# OpenProg-18F2550-etch.net
KiCad netlist of a schematic drawn in EAGLE
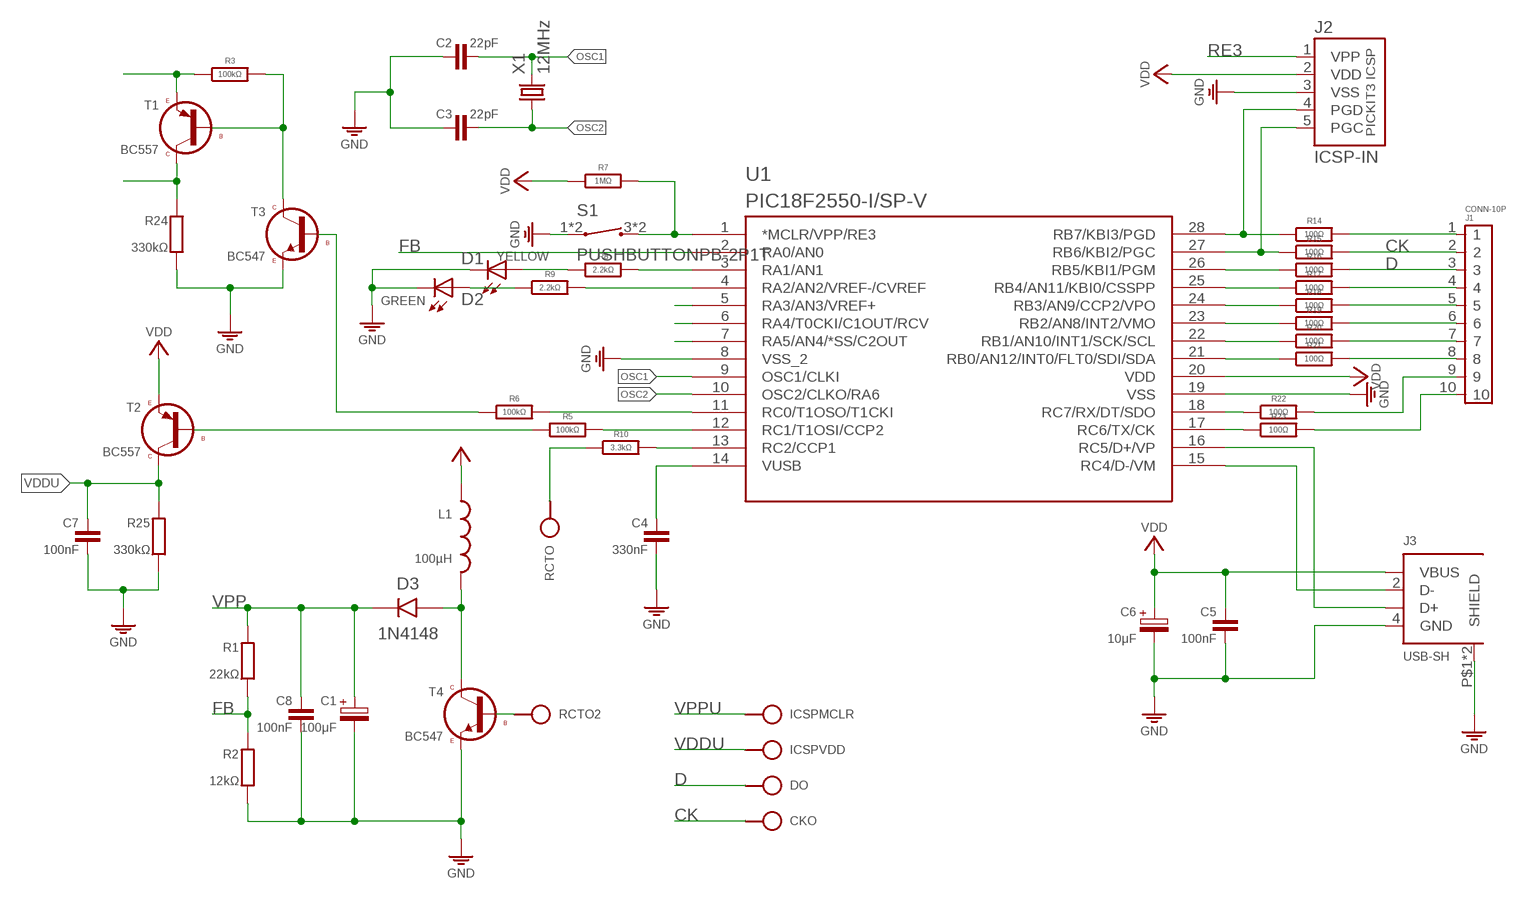
[diagram p0: schematic, sheet 1]

(export (version "E")
  (design (tool "Eeschema 10.0.6"))
  (components
    (comp (ref "C1")
      (value "100μF")
      (footprint "eagle-import:E2,5-5_V")
      (libsource (lib "eagle-import") (part "CPOLE2,5-5/V"))
    )
    (comp (ref "C2")
      (value "22pF")
      (footprint "eagle-import:C025-015X024")
      (libsource (lib "eagle-import") (part "C-H025-015X024"))
    )
    (comp (ref "C3")
      (value "22pF")
      (footprint "eagle-import:C025-015X024")
      (libsource (lib "eagle-import") (part "C-H025-015X024"))
    )
    (comp (ref "C4")
      (value "330nF")
      (footprint "eagle-import:C050-030X075")
      (libsource (lib "eagle-import") (part "C050-030X075"))
    )
    (comp (ref "C5")
      (value "100nF")
      (footprint "eagle-import:C025-015X024")
      (libsource (lib "eagle-import") (part "C025-015X024"))
    )
    (comp (ref "C6")
      (value "10μF")
      (footprint "eagle-import:E2,5-5")
      (libsource (lib "eagle-import") (part "CPOLE2.5-5"))
    )
    (comp (ref "C7")
      (value "100nF")
      (footprint "eagle-import:C025-015X024")
      (libsource (lib "eagle-import") (part "C025-015X024"))
    )
    (comp (ref "C8")
      (value "100nF")
      (footprint "eagle-import:C025-015X024")
      (libsource (lib "eagle-import") (part "C025-015X024"))
    )
    (comp (ref "CKO")
      (value "HPORT")
      (footprint "eagle-import:SPAD")
      (libsource (lib "eagle-import") (part "HPORT"))
    )
    (comp (ref "D1")
      (value "YELLOW")
      (footprint "eagle-import:LED_3MM")
      (libsource (lib "eagle-import") (part "LED-3MM"))
    )
    (comp (ref "D2")
      (value "GREEN")
      (footprint "eagle-import:LED_3MM")
      (libsource (lib "eagle-import") (part "LED-3MM"))
    )
    (comp (ref "D3")
      (value "1N4148")
      (footprint "eagle-import:DO34-7")
      (libsource (lib "eagle-import") (part "1N4148-HDO34-7"))
    )
    (comp (ref "DO")
      (value "HPORT")
      (footprint "eagle-import:SPAD")
      (libsource (lib "eagle-import") (part "HPORT"))
    )
    (comp (ref "ICSPMCLR")
      (value "HPORT")
      (footprint "eagle-import:SPAD")
      (libsource (lib "eagle-import") (part "HPORT"))
    )
    (comp (ref "ICSPVDD")
      (value "HPORT")
      (footprint "eagle-import:SPAD")
      (libsource (lib "eagle-import") (part "HPORT"))
    )
    (comp (ref "J1")
      (value "CONN-10P")
      (footprint "eagle-import:CONN-10P")
      (libsource (lib "eagle-import") (part "CONN-10P"))
    )
    (comp (ref "J2")
      (value "ICSP-IN")
      (footprint "eagle-import:PIC-PK3")
      (libsource (lib "eagle-import") (part "PICKIT3-ICSP-PK3"))
    )
    (comp (ref "J3")
      (value "USB-SH")
      (footprint "eagle-import:USB-B-PRINT")
      (libsource (lib "eagle-import") (part "USB-SH"))
    )
    (comp (ref "L1")
      (value "100µH")
      (footprint "eagle-import:L-03_10V")
      (libsource (lib "eagle-import") (part "L02/10"))
    )
    (comp (ref "R1")
      (value "22kΩ")
      (footprint "eagle-import:0204_10-V")
      (libsource (lib "eagle-import") (part "R0204/10-V"))
    )
    (comp (ref "R2")
      (value "12kΩ")
      (footprint "eagle-import:0204_10-V")
      (libsource (lib "eagle-import") (part "R0204/10-V"))
    )
    (comp (ref "R3")
      (value "100kΩ")
      (footprint "eagle-import:0204_2")
      (libsource (lib "eagle-import") (part "R-H0204/2"))
    )
    (comp (ref "R5")
      (value "100kΩ")
      (footprint "eagle-import:0204_10")
      (libsource (lib "eagle-import") (part "R-H0204/10"))
    )
    (comp (ref "R6")
      (value "100kΩ")
      (footprint "eagle-import:0204_10")
      (libsource (lib "eagle-import") (part "R-H0204/10"))
    )
    (comp (ref "R7")
      (value "1MΩ")
      (footprint "eagle-import:0204_10-V")
      (libsource (lib "eagle-import") (part "R-H0204/10-V"))
    )
    (comp (ref "R8")
      (value "2.2kΩ")
      (footprint "eagle-import:0204_10")
      (libsource (lib "eagle-import") (part "R-H0204/10"))
    )
    (comp (ref "R9")
      (value "2.2kΩ")
      (footprint "eagle-import:0204_10")
      (libsource (lib "eagle-import") (part "R-H0204/10"))
    )
    (comp (ref "R10")
      (value "3.3kΩ")
      (footprint "eagle-import:0204_10")
      (libsource (lib "eagle-import") (part "R-H0204/10"))
    )
    (comp (ref "R14")
      (value "100Ω")
      (footprint "eagle-import:0204_10")
      (libsource (lib "eagle-import") (part "R-H0204/10"))
    )
    (comp (ref "R15")
      (value "100Ω")
      (footprint "eagle-import:0204_10")
      (libsource (lib "eagle-import") (part "R-H0204/10"))
    )
    (comp (ref "R16")
      (value "100Ω")
      (footprint "eagle-import:0204_10")
      (libsource (lib "eagle-import") (part "R-H0204/10"))
    )
    (comp (ref "R17")
      (value "100Ω")
      (footprint "eagle-import:0204_10")
      (libsource (lib "eagle-import") (part "R-H0204/10"))
    )
    (comp (ref "R18")
      (value "100Ω")
      (footprint "eagle-import:0204_10")
      (libsource (lib "eagle-import") (part "R-H0204/10"))
    )
    (comp (ref "R19")
      (value "100Ω")
      (footprint "eagle-import:0204_10")
      (libsource (lib "eagle-import") (part "R-H0204/10"))
    )
    (comp (ref "R20")
      (value "100Ω")
      (footprint "eagle-import:0204_10")
      (libsource (lib "eagle-import") (part "R-H0204/10"))
    )
    (comp (ref "R21")
      (value "100Ω")
      (footprint "eagle-import:0204_10")
      (libsource (lib "eagle-import") (part "R-H0204/10"))
    )
    (comp (ref "R22")
      (value "100Ω")
      (footprint "eagle-import:0204_10")
      (libsource (lib "eagle-import") (part "R-H0204/10"))
    )
    (comp (ref "R23")
      (value "100Ω")
      (footprint "eagle-import:0204_10")
      (libsource (lib "eagle-import") (part "R-H0204/10"))
    )
    (comp (ref "R24")
      (value "330kΩ")
      (footprint "eagle-import:0204_10-V")
      (libsource (lib "eagle-import") (part "R0204/10-V"))
    )
    (comp (ref "R25")
      (value "330kΩ")
      (footprint "eagle-import:0204_10-V")
      (libsource (lib "eagle-import") (part "R0204/10-V"))
    )
    (comp (ref "RCTO")
      (value "HPORT")
      (footprint "eagle-import:SPAD")
      (libsource (lib "eagle-import") (part "HPORT"))
    )
    (comp (ref "RCTO2")
      (value "HPORT")
      (footprint "eagle-import:SPAD")
      (libsource (lib "eagle-import") (part "HPORT"))
    )
    (comp (ref "S1")
      (value "PUSHBUTTONPB-2P1T")
      (footprint "eagle-import:PB-2P1T")
      (libsource (lib "eagle-import") (part "PUSHBUTTONPB-2P1T"))
    )
    (comp (ref "T1")
      (value "BC557")
      (footprint "eagle-import:TO92-CBE")
      (libsource (lib "eagle-import") (part "BC557CBE"))
    )
    (comp (ref "T2")
      (value "BC557")
      (footprint "eagle-import:TO92-CBE")
      (libsource (lib "eagle-import") (part "BC557CBE"))
    )
    (comp (ref "T3")
      (value "BC547")
      (footprint "eagle-import:TO92")
      (libsource (lib "eagle-import") (part "BC547"))
    )
    (comp (ref "T4")
      (value "BC547")
      (footprint "eagle-import:TO92")
      (libsource (lib "eagle-import") (part "BC547"))
    )
    (comp (ref "U1")
      (value "PIC18F2550-I/SP-V")
      (footprint "eagle-import:DIL28-3_V")
      (libsource (lib "eagle-import") (part "PIC18F2550-I/SP-V"))
    )
    (comp (ref "X1")
      (value "12MHz")
      (footprint "eagle-import:HC49")
      (libsource (lib "eagle-import") (part "CRYSTALHC49"))
    )
  )
  (nets
    (net (code "1") (name "/CK") (class "Default")
      (node (ref "CKO") (pin "1") (pinfunction "P$1_1") (pintype "passive"))
      (node (ref "J1") (pin "2") (pinfunction "2_2") (pintype "passive"))
      (node (ref "R15") (pin "2") (pinfunction "2_2") (pintype "passive"))
    )
    (net (code "2") (name "/D") (class "Default")
      (node (ref "DO") (pin "1") (pinfunction "P$1_1") (pintype "passive"))
      (node (ref "J1") (pin "3") (pinfunction "3_3") (pintype "passive"))
      (node (ref "R16") (pin "2") (pinfunction "2_2") (pintype "passive"))
    )
    (net (code "3") (name "/FB") (class "Default")
      (node (ref "R1") (pin "2") (pinfunction "1_2") (pintype "passive"))
      (node (ref "R2") (pin "1") (pinfunction "2_1") (pintype "passive"))
      (node (ref "U1") (pin "2") (pinfunction "RA0/AN0_2") (pintype "passive"))
    )
    (net (code "4") (name "/RE3") (class "Default")
      (node (ref "J2") (pin "1") (pinfunction "VPP_1") (pintype "passive"))
      (node (ref "R7") (pin "2") (pinfunction "2_2") (pintype "passive"))
      (node (ref "S1") (pin "3") (pinfunction "2_3") (pintype "passive"))
      (node (ref "S1") (pin "4") (pinfunction "2_4") (pintype "passive"))
      (node (ref "U1") (pin "1") (pinfunction "*MCLR/VPP/RE3_1") (pintype "passive"))
    )
    (net (code "5") (name "/VPP") (class "Default")
      (node (ref "C1") (pin "+") (pinfunction "+_+") (pintype "passive"))
      (node (ref "C8") (pin "1") (pinfunction "1_1") (pintype "passive"))
      (node (ref "D3") (pin "C") (pinfunction "C_C") (pintype "passive"))
      (node (ref "R1") (pin "1") (pinfunction "2_1") (pintype "passive"))
      (node (ref "R3") (pin "1") (pinfunction "1_1") (pintype "passive"))
      (node (ref "T1") (pin "3") (pinfunction "E_3") (pintype "passive"))
    )
    (net (code "6") (name "/VPPU") (class "Default")
      (node (ref "ICSPMCLR") (pin "1") (pinfunction "P$1_1") (pintype "passive"))
      (node (ref "R24") (pin "1") (pinfunction "2_1") (pintype "passive"))
      (node (ref "T1") (pin "1") (pinfunction "C_1") (pintype "passive"))
    )
    (net (code "7") (name "GND") (class "Default")
      (node (ref "C1") (pin "-") (pinfunction "-_-") (pintype "passive"))
      (node (ref "C2") (pin "1") (pinfunction "1_1") (pintype "passive"))
      (node (ref "C3") (pin "1") (pinfunction "1_1") (pintype "passive"))
      (node (ref "C4") (pin "2") (pinfunction "2_2") (pintype "passive"))
      (node (ref "C5") (pin "2") (pinfunction "2_2") (pintype "passive"))
      (node (ref "C6") (pin "-") (pinfunction "-_-") (pintype "passive"))
      (node (ref "C7") (pin "2") (pinfunction "2_2") (pintype "passive"))
      (node (ref "C8") (pin "2") (pinfunction "2_2") (pintype "passive"))
      (node (ref "D1") (pin "K") (pinfunction "C_K") (pintype "passive"))
      (node (ref "D2") (pin "K") (pinfunction "C_K") (pintype "passive"))
      (node (ref "J2") (pin "3") (pinfunction "VSS_3") (pintype "passive"))
      (node (ref "J3") (pin "4") (pinfunction "GND_4") (pintype "bidirectional"))
      (node (ref "J3") (pin "P$1") (pinfunction "SHIELD_P$1") (pintype "bidirectional"))
      (node (ref "J3") (pin "P$2") (pinfunction "SHIELD_P$2") (pintype "bidirectional"))
      (node (ref "R2") (pin "2") (pinfunction "1_2") (pintype "passive"))
      (node (ref "R24") (pin "2") (pinfunction "1_2") (pintype "passive"))
      (node (ref "R25") (pin "2") (pinfunction "1_2") (pintype "passive"))
      (node (ref "S1") (pin "1") (pinfunction "1_1") (pintype "passive"))
      (node (ref "S1") (pin "2") (pinfunction "1_2") (pintype "passive"))
      (node (ref "T3") (pin "3") (pinfunction "E_3") (pintype "passive"))
      (node (ref "T4") (pin "3") (pinfunction "E_3") (pintype "passive"))
      (node (ref "U1") (pin "19") (pinfunction "VSS_19") (pintype "passive"))
      (node (ref "U1") (pin "8") (pinfunction "VSS_2_8") (pintype "passive"))
    )
    (net (code "8") (name "Net-(D1-PadA)") (class "Default")
      (node (ref "D1") (pin "A") (pinfunction "A_A") (pintype "passive"))
      (node (ref "R8") (pin "1") (pinfunction "1_1") (pintype "passive"))
    )
    (net (code "9") (name "Net-(D2-PadA)") (class "Default")
      (node (ref "D2") (pin "A") (pinfunction "A_A") (pintype "passive"))
      (node (ref "R9") (pin "1") (pinfunction "1_1") (pintype "passive"))
    )
    (net (code "10") (name "Net-(J1-Pad1)") (class "Default")
      (node (ref "J1") (pin "1") (pinfunction "1_1") (pintype "passive"))
      (node (ref "R14") (pin "2") (pinfunction "2_2") (pintype "passive"))
    )
    (net (code "11") (name "Net-(J1-Pad4)") (class "Default")
      (node (ref "J1") (pin "4") (pinfunction "4_4") (pintype "passive"))
      (node (ref "R17") (pin "2") (pinfunction "2_2") (pintype "passive"))
    )
    (net (code "12") (name "Net-(J1-Pad5)") (class "Default")
      (node (ref "J1") (pin "5") (pinfunction "5_5") (pintype "passive"))
      (node (ref "R18") (pin "2") (pinfunction "2_2") (pintype "passive"))
    )
    (net (code "13") (name "Net-(J1-Pad6)") (class "Default")
      (node (ref "J1") (pin "6") (pinfunction "6_6") (pintype "passive"))
      (node (ref "R19") (pin "2") (pinfunction "2_2") (pintype "passive"))
    )
    (net (code "14") (name "Net-(J1-Pad7)") (class "Default")
      (node (ref "J1") (pin "7") (pinfunction "7_7") (pintype "passive"))
      (node (ref "R20") (pin "2") (pinfunction "2_2") (pintype "passive"))
    )
    (net (code "15") (name "Net-(J1-Pad8)") (class "Default")
      (node (ref "J1") (pin "8") (pinfunction "8_8") (pintype "passive"))
      (node (ref "R21") (pin "2") (pinfunction "2_2") (pintype "passive"))
    )
    (net (code "16") (name "Net-(J1-Pad9)") (class "Default")
      (node (ref "J1") (pin "9") (pinfunction "9_9") (pintype "passive"))
      (node (ref "R22") (pin "2") (pinfunction "2_2") (pintype "passive"))
    )
    (net (code "17") (name "Net-(J1-Pad10)") (class "Default")
      (node (ref "J1") (pin "10") (pinfunction "10_10") (pintype "passive"))
      (node (ref "R23") (pin "2") (pinfunction "2_2") (pintype "passive"))
    )
    (net (code "18") (name "Net-(J2-PGC)") (class "Default")
      (node (ref "J2") (pin "5") (pinfunction "PGC_5") (pintype "passive"))
      (node (ref "R15") (pin "1") (pinfunction "1_1") (pintype "passive"))
      (node (ref "U1") (pin "27") (pinfunction "RB6/KBI2/PGC_27") (pintype "passive"))
    )
    (net (code "19") (name "Net-(J2-PGD)") (class "Default")
      (node (ref "J2") (pin "4") (pinfunction "PGD_4") (pintype "passive"))
      (node (ref "R14") (pin "1") (pinfunction "1_1") (pintype "passive"))
      (node (ref "U1") (pin "28") (pinfunction "RB7/KBI3/PGD_28") (pintype "passive"))
    )
    (net (code "20") (name "Net-(J3-D+)") (class "Default")
      (node (ref "J3") (pin "3") (pinfunction "D+_3") (pintype "bidirectional"))
      (node (ref "U1") (pin "16") (pinfunction "RC5/D+/VP_16") (pintype "passive"))
    )
    (net (code "21") (name "Net-(J3-D-)") (class "Default")
      (node (ref "J3") (pin "2") (pinfunction "D-_2") (pintype "bidirectional"))
      (node (ref "U1") (pin "15") (pinfunction "RC4/D-/VM_15") (pintype "passive"))
    )
    (net (code "22") (name "Net-(RCTO-P$1)") (class "Default")
      (node (ref "R10") (pin "1") (pinfunction "1_1") (pintype "passive"))
      (node (ref "RCTO") (pin "1") (pinfunction "P$1_1") (pintype "passive"))
    )
    (net (code "23") (name "Net-(RCTO2-P$1)") (class "Default")
      (node (ref "RCTO2") (pin "1") (pinfunction "P$1_1") (pintype "passive"))
      (node (ref "T4") (pin "2") (pinfunction "B_2") (pintype "passive"))
    )
    (net (code "24") (name "Net-(T1-B)") (class "Default")
      (node (ref "R3") (pin "2") (pinfunction "2_2") (pintype "passive"))
      (node (ref "T1") (pin "2") (pinfunction "B_2") (pintype "passive"))
      (node (ref "T3") (pin "1") (pinfunction "C_1") (pintype "passive"))
    )
    (net (code "25") (name "Net-(T2-B)") (class "Default")
      (node (ref "R5") (pin "1") (pinfunction "1_1") (pintype "passive"))
      (node (ref "T2") (pin "2") (pinfunction "B_2") (pintype "passive"))
    )
    (net (code "26") (name "Net-(T3-B)") (class "Default")
      (node (ref "R6") (pin "1") (pinfunction "1_1") (pintype "passive"))
      (node (ref "T3") (pin "2") (pinfunction "B_2") (pintype "passive"))
    )
    (net (code "27") (name "Net-(T4-C)") (class "Default")
      (node (ref "D3") (pin "A") (pinfunction "A_A") (pintype "passive"))
      (node (ref "L1") (pin "2") (pinfunction "2_2") (pintype "passive"))
      (node (ref "T4") (pin "1") (pinfunction "C_1") (pintype "passive"))
    )
    (net (code "28") (name "Net-(U1-RA1{slash}AN1)") (class "Default")
      (node (ref "R8") (pin "2") (pinfunction "2_2") (pintype "passive"))
      (node (ref "U1") (pin "3") (pinfunction "RA1/AN1_3") (pintype "passive"))
    )
    (net (code "29") (name "Net-(U1-RA2{slash}AN2{slash}VREF-{slash}CVREF)") (class "Default")
      (node (ref "R9") (pin "2") (pinfunction "2_2") (pintype "passive"))
      (node (ref "U1") (pin "4") (pinfunction "RA2/AN2/VREF-/CVREF_4") (pintype "passive"))
    )
    (net (code "30") (name "Net-(U1-RB0{slash}AN12{slash}INT0{slash}FLT0{slash}SDI{slash}SDA)") (class "Default")
      (node (ref "R21") (pin "1") (pinfunction "1_1") (pintype "passive"))
      (node (ref "U1") (pin "21") (pinfunction "RB0/AN12/INT0/FLT0/SDI/SDA_21") (pintype "passive"))
    )
    (net (code "31") (name "Net-(U1-RB1{slash}AN10{slash}INT1{slash}SCK{slash}SCL)") (class "Default")
      (node (ref "R20") (pin "1") (pinfunction "1_1") (pintype "passive"))
      (node (ref "U1") (pin "22") (pinfunction "RB1/AN10/INT1/SCK/SCL_22") (pintype "passive"))
    )
    (net (code "32") (name "Net-(U1-RB2{slash}AN8{slash}INT2{slash}VMO)") (class "Default")
      (node (ref "R19") (pin "1") (pinfunction "1_1") (pintype "passive"))
      (node (ref "U1") (pin "23") (pinfunction "RB2/AN8/INT2/VMO_23") (pintype "passive"))
    )
    (net (code "33") (name "Net-(U1-RB3{slash}AN9{slash}CCP2{slash}VPO)") (class "Default")
      (node (ref "R18") (pin "1") (pinfunction "1_1") (pintype "passive"))
      (node (ref "U1") (pin "24") (pinfunction "RB3/AN9/CCP2/VPO_24") (pintype "passive"))
    )
    (net (code "34") (name "Net-(U1-RB4{slash}AN11{slash}KBI0{slash}CSSPP)") (class "Default")
      (node (ref "R17") (pin "1") (pinfunction "1_1") (pintype "passive"))
      (node (ref "U1") (pin "25") (pinfunction "RB4/AN11/KBI0/CSSPP_25") (pintype "passive"))
    )
    (net (code "35") (name "Net-(U1-RB5{slash}KBI1{slash}PGM)") (class "Default")
      (node (ref "R16") (pin "1") (pinfunction "1_1") (pintype "passive"))
      (node (ref "U1") (pin "26") (pinfunction "RB5/KBI1/PGM_26") (pintype "passive"))
    )
    (net (code "36") (name "Net-(U1-RC0{slash}T1OSO{slash}T1CKI)") (class "Default")
      (node (ref "R6") (pin "2") (pinfunction "2_2") (pintype "passive"))
      (node (ref "U1") (pin "11") (pinfunction "RC0/T1OSO/T1CKI_11") (pintype "passive"))
    )
    (net (code "37") (name "Net-(U1-RC1{slash}T1OSI{slash}CCP2)") (class "Default")
      (node (ref "R5") (pin "2") (pinfunction "2_2") (pintype "passive"))
      (node (ref "U1") (pin "12") (pinfunction "RC1/T1OSI/CCP2_12") (pintype "passive"))
    )
    (net (code "38") (name "Net-(U1-RC2{slash}CCP1)") (class "Default")
      (node (ref "R10") (pin "2") (pinfunction "2_2") (pintype "passive"))
      (node (ref "U1") (pin "13") (pinfunction "RC2/CCP1_13") (pintype "passive"))
    )
    (net (code "39") (name "Net-(U1-RC6{slash}TX{slash}CK)") (class "Default")
      (node (ref "R23") (pin "1") (pinfunction "1_1") (pintype "passive"))
      (node (ref "U1") (pin "17") (pinfunction "RC6/TX/CK_17") (pintype "passive"))
    )
    (net (code "40") (name "Net-(U1-RC7{slash}RX{slash}DT{slash}SDO)") (class "Default")
      (node (ref "R22") (pin "1") (pinfunction "1_1") (pintype "passive"))
      (node (ref "U1") (pin "18") (pinfunction "RC7/RX/DT/SDO_18") (pintype "passive"))
    )
    (net (code "41") (name "Net-(U1-VUSB)") (class "Default")
      (node (ref "C4") (pin "1") (pinfunction "1_1") (pintype "passive"))
      (node (ref "U1") (pin "14") (pinfunction "VUSB_14") (pintype "passive"))
    )
    (net (code "42") (name "OSC1") (class "Default")
      (node (ref "C2") (pin "2") (pinfunction "2_2") (pintype "passive"))
      (node (ref "U1") (pin "9") (pinfunction "OSC1/CLKI_9") (pintype "passive"))
      (node (ref "X1") (pin "2") (pinfunction "2_2") (pintype "passive"))
    )
    (net (code "43") (name "OSC2") (class "Default")
      (node (ref "C3") (pin "2") (pinfunction "2_2") (pintype "passive"))
      (node (ref "U1") (pin "10") (pinfunction "OSC2/CLKO/RA6_10") (pintype "passive"))
      (node (ref "X1") (pin "1") (pinfunction "1_1") (pintype "passive"))
    )
    (net (code "44") (name "VDD") (class "Default")
      (node (ref "C5") (pin "1") (pinfunction "1_1") (pintype "passive"))
      (node (ref "C6") (pin "+") (pinfunction "+_+") (pintype "passive"))
      (node (ref "J2") (pin "2") (pinfunction "VDD_2") (pintype "passive"))
      (node (ref "J3") (pin "1") (pinfunction "VBUS_1") (pintype "bidirectional"))
      (node (ref "L1") (pin "1") (pinfunction "1_1") (pintype "passive"))
      (node (ref "R7") (pin "1") (pinfunction "1_1") (pintype "passive"))
      (node (ref "T2") (pin "3") (pinfunction "E_3") (pintype "passive"))
      (node (ref "U1") (pin "20") (pinfunction "VDD_20") (pintype "passive"))
    )
    (net (code "45") (name "VDDU") (class "Default")
      (node (ref "C7") (pin "1") (pinfunction "1_1") (pintype "passive"))
      (node (ref "ICSPVDD") (pin "1") (pinfunction "P$1_1") (pintype "passive"))
      (node (ref "R25") (pin "1") (pinfunction "2_1") (pintype "passive"))
      (node (ref "T2") (pin "1") (pinfunction "C_1") (pintype "passive"))
    )
    (net (code "46") (name "unconnected-(U1-RA3{slash}AN3{slash}VREF+-Pad5)") (class "Default")
      (node (ref "U1") (pin "5") (pinfunction "RA3/AN3/VREF+_5") (pintype "passive"))
    )
    (net (code "47") (name "unconnected-(U1-RA4{slash}T0CKI{slash}C1OUT{slash}RCV-Pad6)") (class "Default")
      (node (ref "U1") (pin "6") (pinfunction "RA4/T0CKI/C1OUT/RCV_6") (pintype "passive"))
    )
    (net (code "48") (name "unconnected-(U1-RA5{slash}AN4{slash}*SS{slash}C2OUT-Pad7)") (class "Default")
      (node (ref "U1") (pin "7") (pinfunction "RA5/AN4/*SS/C2OUT_7") (pintype "passive"))
    )
  )
)
